# Switch_Breakout_-_Schematic.net
KiCad netlist of a schematic drawn in EAGLE
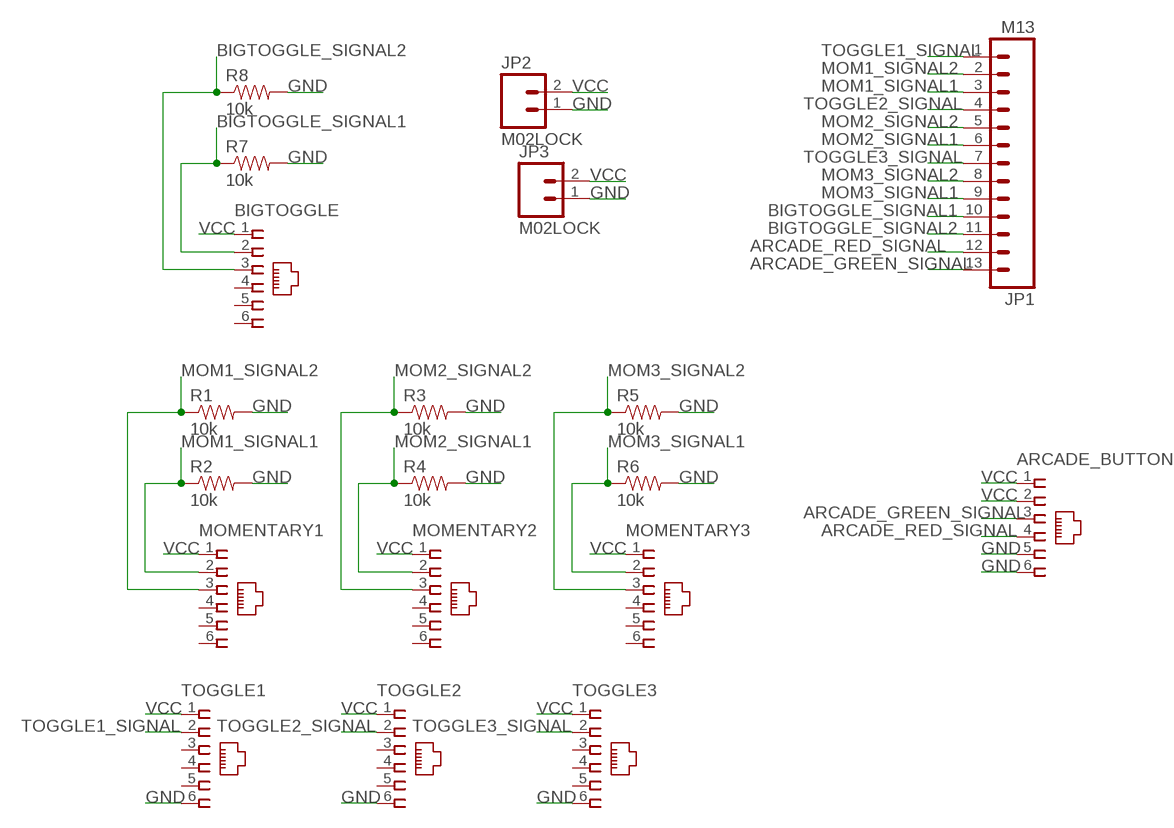
[diagram p0: schematic, sheet 1]

(export (version "E")
  (design (tool "Eeschema 10.0.6"))
  (components
    (comp (ref "ARCADE_BUTTONS")
      (value "555165-1")
      (footprint "eagle-import:555165-1")
      (libsource (lib "eagle-import") (part "555165-1"))
    )
    (comp (ref "BIGTOGGLE")
      (value "555165-1")
      (footprint "eagle-import:555165-1")
      (libsource (lib "eagle-import") (part "555165-1"))
    )
    (comp (ref "JP1")
      (value "M13")
      (footprint "eagle-import:1X13")
      (libsource (lib "eagle-import") (part "M13"))
    )
    (comp (ref "JP2")
      (value "M02LOCK")
      (footprint "eagle-import:1X02_LOCK")
      (libsource (lib "eagle-import") (part "M02LOCK"))
    )
    (comp (ref "JP3")
      (value "M02LOCK")
      (footprint "eagle-import:1X02_LOCK")
      (libsource (lib "eagle-import") (part "M02LOCK"))
    )
    (comp (ref "MOMENTARY1")
      (value "555165-1")
      (footprint "eagle-import:555165-1")
      (libsource (lib "eagle-import") (part "555165-1"))
    )
    (comp (ref "MOMENTARY2")
      (value "555165-1")
      (footprint "eagle-import:555165-1")
      (libsource (lib "eagle-import") (part "555165-1"))
    )
    (comp (ref "MOMENTARY3")
      (value "555165-1")
      (footprint "eagle-import:555165-1")
      (libsource (lib "eagle-import") (part "555165-1"))
    )
    (comp (ref "R1")
      (value "10k")
      (footprint "eagle-import:0603-RES")
      (libsource (lib "eagle-import") (part "RESISTOR0603"))
    )
    (comp (ref "R2")
      (value "10k")
      (footprint "eagle-import:0603-RES")
      (libsource (lib "eagle-import") (part "RESISTOR0603"))
    )
    (comp (ref "R3")
      (value "10k")
      (footprint "eagle-import:0603-RES")
      (libsource (lib "eagle-import") (part "RESISTOR0603"))
    )
    (comp (ref "R4")
      (value "10k")
      (footprint "eagle-import:0603-RES")
      (libsource (lib "eagle-import") (part "RESISTOR0603"))
    )
    (comp (ref "R5")
      (value "10k")
      (footprint "eagle-import:0603-RES")
      (libsource (lib "eagle-import") (part "RESISTOR0603"))
    )
    (comp (ref "R6")
      (value "10k")
      (footprint "eagle-import:0603-RES")
      (libsource (lib "eagle-import") (part "RESISTOR0603"))
    )
    (comp (ref "R7")
      (value "10k")
      (footprint "eagle-import:0603-RES")
      (libsource (lib "eagle-import") (part "RESISTOR0603"))
    )
    (comp (ref "R8")
      (value "10k")
      (footprint "eagle-import:0603-RES")
      (libsource (lib "eagle-import") (part "RESISTOR0603"))
    )
    (comp (ref "TOGGLE1")
      (value "555165-1")
      (footprint "eagle-import:555165-1")
      (libsource (lib "eagle-import") (part "555165-1"))
    )
    (comp (ref "TOGGLE2")
      (value "555165-1")
      (footprint "eagle-import:555165-1")
      (libsource (lib "eagle-import") (part "555165-1"))
    )
    (comp (ref "TOGGLE3")
      (value "555165-1")
      (footprint "eagle-import:555165-1")
      (libsource (lib "eagle-import") (part "555165-1"))
    )
  )
  (nets
    (net (code "1") (name "/ARCADE_GREEN_SIGNAL") (class "Default")
      (node (ref "ARCADE_BUTTONS") (pin "3") (pinfunction "3_3") (pintype "passive"))
      (node (ref "JP1") (pin "13") (pinfunction "13_13") (pintype "passive"))
    )
    (net (code "2") (name "/ARCADE_RED_SIGNAL") (class "Default")
      (node (ref "ARCADE_BUTTONS") (pin "4") (pinfunction "4_4") (pintype "passive"))
      (node (ref "JP1") (pin "12") (pinfunction "12_12") (pintype "passive"))
    )
    (net (code "3") (name "/BIGTOGGLE_SIGNAL1") (class "Default")
      (node (ref "BIGTOGGLE") (pin "2") (pinfunction "2_2") (pintype "passive"))
      (node (ref "JP1") (pin "10") (pinfunction "10_10") (pintype "passive"))
      (node (ref "R7") (pin "1") (pinfunction "1_1") (pintype "passive"))
    )
    (net (code "4") (name "/BIGTOGGLE_SIGNAL2") (class "Default")
      (node (ref "BIGTOGGLE") (pin "3") (pinfunction "3_3") (pintype "passive"))
      (node (ref "JP1") (pin "11") (pinfunction "11_11") (pintype "passive"))
      (node (ref "R8") (pin "1") (pinfunction "1_1") (pintype "passive"))
    )
    (net (code "5") (name "/GND") (class "Default")
      (node (ref "ARCADE_BUTTONS") (pin "5") (pinfunction "5_5") (pintype "passive"))
      (node (ref "ARCADE_BUTTONS") (pin "6") (pinfunction "6_6") (pintype "passive"))
      (node (ref "JP2") (pin "1") (pinfunction "1_1") (pintype "passive"))
      (node (ref "JP3") (pin "1") (pinfunction "1_1") (pintype "passive"))
      (node (ref "R1") (pin "2") (pinfunction "2_2") (pintype "passive"))
      (node (ref "R2") (pin "2") (pinfunction "2_2") (pintype "passive"))
      (node (ref "R3") (pin "2") (pinfunction "2_2") (pintype "passive"))
      (node (ref "R4") (pin "2") (pinfunction "2_2") (pintype "passive"))
      (node (ref "R5") (pin "2") (pinfunction "2_2") (pintype "passive"))
      (node (ref "R6") (pin "2") (pinfunction "2_2") (pintype "passive"))
      (node (ref "R7") (pin "2") (pinfunction "2_2") (pintype "passive"))
      (node (ref "R8") (pin "2") (pinfunction "2_2") (pintype "passive"))
      (node (ref "TOGGLE1") (pin "6") (pinfunction "6_6") (pintype "passive"))
      (node (ref "TOGGLE2") (pin "6") (pinfunction "6_6") (pintype "passive"))
      (node (ref "TOGGLE3") (pin "6") (pinfunction "6_6") (pintype "passive"))
    )
    (net (code "6") (name "/MOM1_SIGNAL1") (class "Default")
      (node (ref "JP1") (pin "3") (pinfunction "3_3") (pintype "passive"))
      (node (ref "MOMENTARY1") (pin "2") (pinfunction "2_2") (pintype "passive"))
      (node (ref "R2") (pin "1") (pinfunction "1_1") (pintype "passive"))
    )
    (net (code "7") (name "/MOM1_SIGNAL2") (class "Default")
      (node (ref "JP1") (pin "2") (pinfunction "2_2") (pintype "passive"))
      (node (ref "MOMENTARY1") (pin "3") (pinfunction "3_3") (pintype "passive"))
      (node (ref "R1") (pin "1") (pinfunction "1_1") (pintype "passive"))
    )
    (net (code "8") (name "/MOM2_SIGNAL1") (class "Default")
      (node (ref "JP1") (pin "6") (pinfunction "6_6") (pintype "passive"))
      (node (ref "MOMENTARY2") (pin "2") (pinfunction "2_2") (pintype "passive"))
      (node (ref "R4") (pin "1") (pinfunction "1_1") (pintype "passive"))
    )
    (net (code "9") (name "/MOM2_SIGNAL2") (class "Default")
      (node (ref "JP1") (pin "5") (pinfunction "5_5") (pintype "passive"))
      (node (ref "MOMENTARY2") (pin "3") (pinfunction "3_3") (pintype "passive"))
      (node (ref "R3") (pin "1") (pinfunction "1_1") (pintype "passive"))
    )
    (net (code "10") (name "/MOM3_SIGNAL1") (class "Default")
      (node (ref "JP1") (pin "9") (pinfunction "9_9") (pintype "passive"))
      (node (ref "MOMENTARY3") (pin "2") (pinfunction "2_2") (pintype "passive"))
      (node (ref "R6") (pin "1") (pinfunction "1_1") (pintype "passive"))
    )
    (net (code "11") (name "/MOM3_SIGNAL2") (class "Default")
      (node (ref "JP1") (pin "8") (pinfunction "8_8") (pintype "passive"))
      (node (ref "MOMENTARY3") (pin "3") (pinfunction "3_3") (pintype "passive"))
      (node (ref "R5") (pin "1") (pinfunction "1_1") (pintype "passive"))
    )
    (net (code "12") (name "/TOGGLE1_SIGNAL") (class "Default")
      (node (ref "JP1") (pin "1") (pinfunction "1_1") (pintype "passive"))
      (node (ref "TOGGLE1") (pin "2") (pinfunction "2_2") (pintype "passive"))
    )
    (net (code "13") (name "/TOGGLE2_SIGNAL") (class "Default")
      (node (ref "JP1") (pin "4") (pinfunction "4_4") (pintype "passive"))
      (node (ref "TOGGLE2") (pin "2") (pinfunction "2_2") (pintype "passive"))
    )
    (net (code "14") (name "/TOGGLE3_SIGNAL") (class "Default")
      (node (ref "JP1") (pin "7") (pinfunction "7_7") (pintype "passive"))
      (node (ref "TOGGLE3") (pin "2") (pinfunction "2_2") (pintype "passive"))
    )
    (net (code "15") (name "/VCC") (class "Default")
      (node (ref "ARCADE_BUTTONS") (pin "1") (pinfunction "1_1") (pintype "passive"))
      (node (ref "ARCADE_BUTTONS") (pin "2") (pinfunction "2_2") (pintype "passive"))
      (node (ref "BIGTOGGLE") (pin "1") (pinfunction "1_1") (pintype "passive"))
      (node (ref "JP2") (pin "2") (pinfunction "2_2") (pintype "passive"))
      (node (ref "JP3") (pin "2") (pinfunction "2_2") (pintype "passive"))
      (node (ref "MOMENTARY1") (pin "1") (pinfunction "1_1") (pintype "passive"))
      (node (ref "MOMENTARY2") (pin "1") (pinfunction "1_1") (pintype "passive"))
      (node (ref "MOMENTARY3") (pin "1") (pinfunction "1_1") (pintype "passive"))
      (node (ref "TOGGLE1") (pin "1") (pinfunction "1_1") (pintype "passive"))
      (node (ref "TOGGLE2") (pin "1") (pinfunction "1_1") (pintype "passive"))
      (node (ref "TOGGLE3") (pin "1") (pinfunction "1_1") (pintype "passive"))
    )
    (net (code "16") (name "unconnected-(BIGTOGGLE-Pad4)") (class "Default")
      (node (ref "BIGTOGGLE") (pin "4") (pinfunction "4_4") (pintype "passive"))
    )
    (net (code "17") (name "unconnected-(BIGTOGGLE-Pad5)") (class "Default")
      (node (ref "BIGTOGGLE") (pin "5") (pinfunction "5_5") (pintype "passive"))
    )
    (net (code "18") (name "unconnected-(BIGTOGGLE-Pad6)") (class "Default")
      (node (ref "BIGTOGGLE") (pin "6") (pinfunction "6_6") (pintype "passive"))
    )
    (net (code "19") (name "unconnected-(MOMENTARY1-Pad4)") (class "Default")
      (node (ref "MOMENTARY1") (pin "4") (pinfunction "4_4") (pintype "passive"))
    )
    (net (code "20") (name "unconnected-(MOMENTARY1-Pad5)") (class "Default")
      (node (ref "MOMENTARY1") (pin "5") (pinfunction "5_5") (pintype "passive"))
    )
    (net (code "21") (name "unconnected-(MOMENTARY1-Pad6)") (class "Default")
      (node (ref "MOMENTARY1") (pin "6") (pinfunction "6_6") (pintype "passive"))
    )
    (net (code "22") (name "unconnected-(MOMENTARY2-Pad4)") (class "Default")
      (node (ref "MOMENTARY2") (pin "4") (pinfunction "4_4") (pintype "passive"))
    )
    (net (code "23") (name "unconnected-(MOMENTARY2-Pad5)") (class "Default")
      (node (ref "MOMENTARY2") (pin "5") (pinfunction "5_5") (pintype "passive"))
    )
    (net (code "24") (name "unconnected-(MOMENTARY2-Pad6)") (class "Default")
      (node (ref "MOMENTARY2") (pin "6") (pinfunction "6_6") (pintype "passive"))
    )
    (net (code "25") (name "unconnected-(MOMENTARY3-Pad4)") (class "Default")
      (node (ref "MOMENTARY3") (pin "4") (pinfunction "4_4") (pintype "passive"))
    )
    (net (code "26") (name "unconnected-(MOMENTARY3-Pad5)") (class "Default")
      (node (ref "MOMENTARY3") (pin "5") (pinfunction "5_5") (pintype "passive"))
    )
    (net (code "27") (name "unconnected-(MOMENTARY3-Pad6)") (class "Default")
      (node (ref "MOMENTARY3") (pin "6") (pinfunction "6_6") (pintype "passive"))
    )
    (net (code "28") (name "unconnected-(TOGGLE1-Pad3)") (class "Default")
      (node (ref "TOGGLE1") (pin "3") (pinfunction "3_3") (pintype "passive"))
    )
    (net (code "29") (name "unconnected-(TOGGLE1-Pad4)") (class "Default")
      (node (ref "TOGGLE1") (pin "4") (pinfunction "4_4") (pintype "passive"))
    )
    (net (code "30") (name "unconnected-(TOGGLE1-Pad5)") (class "Default")
      (node (ref "TOGGLE1") (pin "5") (pinfunction "5_5") (pintype "passive"))
    )
    (net (code "31") (name "unconnected-(TOGGLE2-Pad3)") (class "Default")
      (node (ref "TOGGLE2") (pin "3") (pinfunction "3_3") (pintype "passive"))
    )
    (net (code "32") (name "unconnected-(TOGGLE2-Pad4)") (class "Default")
      (node (ref "TOGGLE2") (pin "4") (pinfunction "4_4") (pintype "passive"))
    )
    (net (code "33") (name "unconnected-(TOGGLE2-Pad5)") (class "Default")
      (node (ref "TOGGLE2") (pin "5") (pinfunction "5_5") (pintype "passive"))
    )
    (net (code "34") (name "unconnected-(TOGGLE3-Pad3)") (class "Default")
      (node (ref "TOGGLE3") (pin "3") (pinfunction "3_3") (pintype "passive"))
    )
    (net (code "35") (name "unconnected-(TOGGLE3-Pad4)") (class "Default")
      (node (ref "TOGGLE3") (pin "4") (pinfunction "4_4") (pintype "passive"))
    )
    (net (code "36") (name "unconnected-(TOGGLE3-Pad5)") (class "Default")
      (node (ref "TOGGLE3") (pin "5") (pinfunction "5_5") (pintype "passive"))
    )
  )
)
